# Apo_Board_2017_ATmega328SMD_PAM2401.net
KiCad netlist of a schematic drawn in EAGLE
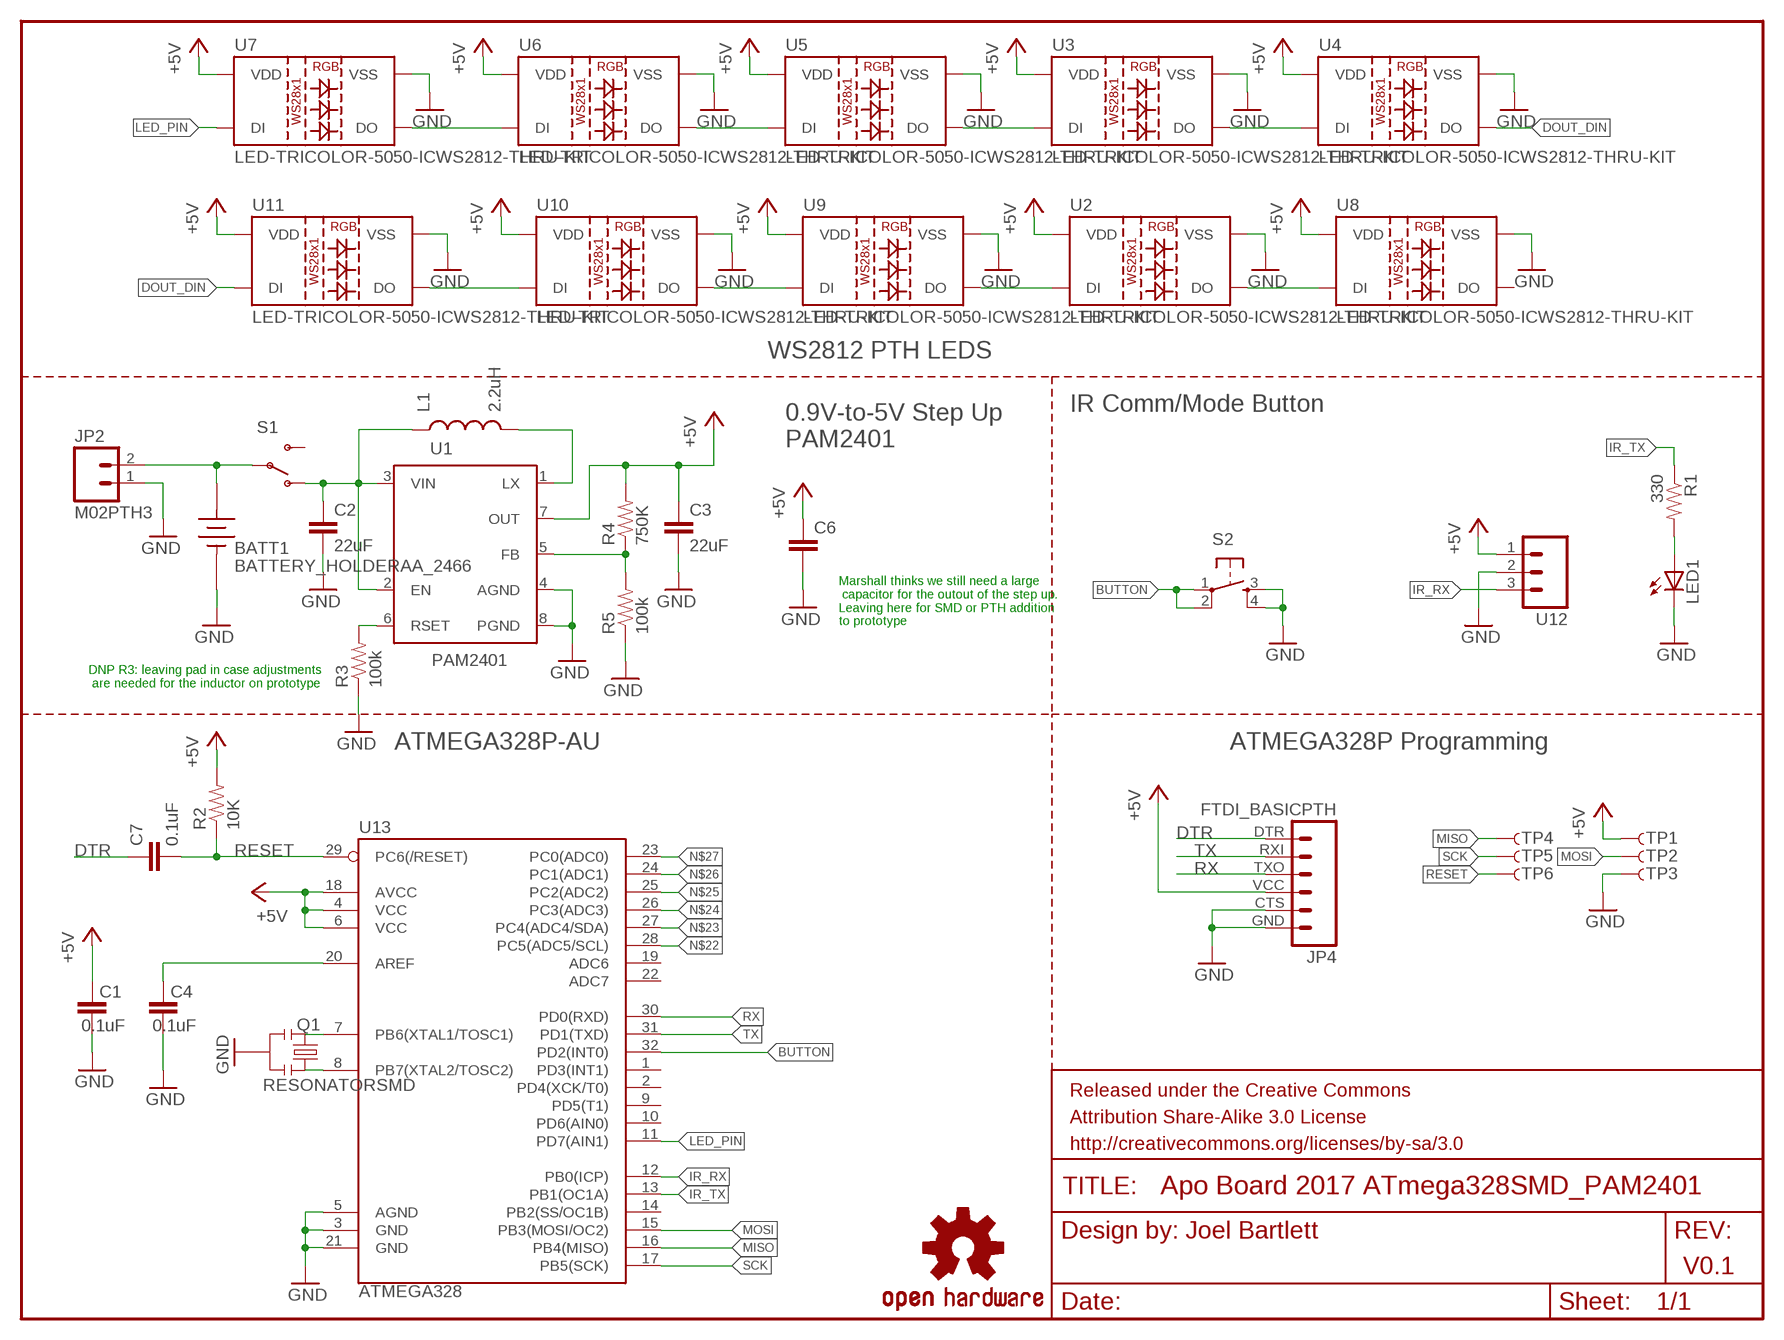
[diagram p0: schematic, sheet 1]

(export (version "E")
  (design (tool "Eeschema 10.0.6"))
  (components
    (comp (ref "BATT1")
      (value "BATTERY_HOLDERAA_2466")
      (footprint "eagle-import:BATT_HOLDER_AA_2466")
      (libsource (lib "eagle-import") (part "BATTERY_HOLDERAA_2466"))
    )
    (comp (ref "C1")
      (value "0.1uF")
      (footprint "eagle-import:0402-CAP")
      (libsource (lib "eagle-import") (part "CAP0402-CAP"))
    )
    (comp (ref "C2")
      (value "22uF")
      (footprint "eagle-import:0805")
      (libsource (lib "eagle-import") (part "22UF-6.3V-20%(0805)"))
    )
    (comp (ref "C3")
      (value "22uF")
      (footprint "eagle-import:0805")
      (libsource (lib "eagle-import") (part "22UF-6.3V-20%(0805)"))
    )
    (comp (ref "C4")
      (value "0.1uF")
      (footprint "eagle-import:0402-CAP")
      (libsource (lib "eagle-import") (part "CAP0402-CAP"))
    )
    (comp (ref "C6")
      (value "CAP1206")
      (footprint "eagle-import:1206")
      (libsource (lib "eagle-import") (part "SparkFun-Capacitors_CAP1206"))
    )
    (comp (ref "C7")
      (value "0.1uF")
      (footprint "eagle-import:0402-CAP")
      (libsource (lib "eagle-import") (part "CAP0402-CAP"))
    )
    (comp (ref "FRAME1")
      (value "FRAME-LETTER")
      (footprint "eagle-import:CREATIVE_COMMONS")
      (libsource (lib "eagle-import") (part "FRAME-LETTER"))
    )
    (comp (ref "JP2")
      (value "M02PTH3")
      (footprint "eagle-import:1X02_LONGPADS")
      (libsource (lib "eagle-import") (part "M02PTH3"))
    )
    (comp (ref "JP4")
      (value "FTDI_BASICPTH")
      (footprint "eagle-import:FTDI_BASIC")
      (libsource (lib "eagle-import") (part "FTDI_BASICPTH"))
    )
    (comp (ref "L1")
      (value "2.2uH")
      (footprint "eagle-import:CR54")
      (libsource (lib "eagle-import") (part "INDUCTORCR54"))
    )
    (comp (ref "LED1")
      (value "LED5MM-KIT")
      (footprint "eagle-import:LED5MM-KIT")
      (libsource (lib "eagle-import") (part "LED5MM-KIT"))
    )
    (comp (ref "LOGO1")
      (value "OSHW-LOGOS")
      (footprint "eagle-import:OSHW-LOGO-S")
      (libsource (lib "eagle-import") (part "OSHW-LOGOS"))
    )
    (comp (ref "Q1")
      (value "RESONATORSMD")
      (footprint "eagle-import:RESONATOR-SMD")
      (libsource (lib "eagle-import") (part "RESONATORSMD"))
    )
    (comp (ref "R1")
      (value "330")
      (footprint "eagle-import:AXIAL-0.3-KIT")
      (libsource (lib "eagle-import") (part "SparkFun-Resistors_RESISTORKIT"))
    )
    (comp (ref "R2")
      (value "10K")
      (footprint "eagle-import:0402-RES")
      (libsource (lib "eagle-import") (part "RESISTOR0402-RES"))
    )
    (comp (ref "R3")
      (value "100k")
      (footprint "eagle-import:0603-RES")
      (libsource (lib "eagle-import") (part "10K-1%RES-00824"))
    )
    (comp (ref "R4")
      (value "750K")
      (footprint "eagle-import:0603-RES")
      (libsource (lib "eagle-import") (part "10K-1%RES-00824"))
    )
    (comp (ref "R5")
      (value "100k")
      (footprint "eagle-import:0603-RES")
      (libsource (lib "eagle-import") (part "10K-1%RES-00824"))
    )
    (comp (ref "S1")
      (value "SWITCH-SPSTKIT")
      (footprint "eagle-import:SWITCH-SPDT_KIT")
      (libsource (lib "eagle-import") (part "SWITCH-SPSTKIT"))
    )
    (comp (ref "S2")
      (value "TAC_SWITCHPTH")
      (footprint "eagle-import:TACTILE-PTH")
      (libsource (lib "eagle-import") (part "TAC_SWITCHPTH"))
    )
    (comp (ref "TP1")
      (value "TP-3x5")
      (footprint "eagle-import:PAD.03X.05")
      (libsource (lib "eagle-import") (part "TEST-POINT3X5"))
    )
    (comp (ref "TP2")
      (value "TP-3x5")
      (footprint "eagle-import:PAD.03X.05")
      (libsource (lib "eagle-import") (part "TEST-POINT3X5"))
    )
    (comp (ref "TP3")
      (value "TP-3x5")
      (footprint "eagle-import:PAD.03X.05")
      (libsource (lib "eagle-import") (part "TEST-POINT3X5"))
    )
    (comp (ref "TP4")
      (value "TP-3x5")
      (footprint "eagle-import:PAD.03X.05")
      (libsource (lib "eagle-import") (part "TEST-POINT3X5"))
    )
    (comp (ref "TP5")
      (value "TP-3x5")
      (footprint "eagle-import:PAD.03X.05")
      (libsource (lib "eagle-import") (part "TEST-POINT3X5"))
    )
    (comp (ref "TP6")
      (value "TP-3x5")
      (footprint "eagle-import:PAD.03X.05")
      (libsource (lib "eagle-import") (part "TEST-POINT3X5"))
    )
    (comp (ref "U1")
      (value "PAM2401")
      (footprint "eagle-import:MSOP8")
      (libsource (lib "eagle-import") (part "PAM2401"))
    )
    (comp (ref "U2")
      (value "LED-TRICOLOR-5050-ICWS2812-THRU-KIT")
      (footprint "eagle-import:LED-RGB-THRU-KIT")
      (libsource (lib "eagle-import") (part "LED-TRICOLOR-5050-ICWS2812-THRU-KIT"))
    )
    (comp (ref "U3")
      (value "LED-TRICOLOR-5050-ICWS2812-THRU-KIT")
      (footprint "eagle-import:LED-RGB-THRU-KIT")
      (libsource (lib "eagle-import") (part "LED-TRICOLOR-5050-ICWS2812-THRU-KIT"))
    )
    (comp (ref "U4")
      (value "LED-TRICOLOR-5050-ICWS2812-THRU-KIT")
      (footprint "eagle-import:LED-RGB-THRU-KIT")
      (libsource (lib "eagle-import") (part "LED-TRICOLOR-5050-ICWS2812-THRU-KIT"))
    )
    (comp (ref "U5")
      (value "LED-TRICOLOR-5050-ICWS2812-THRU-KIT")
      (footprint "eagle-import:LED-RGB-THRU-KIT")
      (libsource (lib "eagle-import") (part "LED-TRICOLOR-5050-ICWS2812-THRU-KIT"))
    )
    (comp (ref "U6")
      (value "LED-TRICOLOR-5050-ICWS2812-THRU-KIT")
      (footprint "eagle-import:LED-RGB-THRU-KIT")
      (libsource (lib "eagle-import") (part "LED-TRICOLOR-5050-ICWS2812-THRU-KIT"))
    )
    (comp (ref "U7")
      (value "LED-TRICOLOR-5050-ICWS2812-THRU-KIT")
      (footprint "eagle-import:LED-RGB-THRU-KIT")
      (libsource (lib "eagle-import") (part "LED-TRICOLOR-5050-ICWS2812-THRU-KIT"))
    )
    (comp (ref "U8")
      (value "LED-TRICOLOR-5050-ICWS2812-THRU-KIT")
      (footprint "eagle-import:LED-RGB-THRU-KIT")
      (libsource (lib "eagle-import") (part "LED-TRICOLOR-5050-ICWS2812-THRU-KIT"))
    )
    (comp (ref "U9")
      (value "LED-TRICOLOR-5050-ICWS2812-THRU-KIT")
      (footprint "eagle-import:LED-RGB-THRU-KIT")
      (libsource (lib "eagle-import") (part "LED-TRICOLOR-5050-ICWS2812-THRU-KIT"))
    )
    (comp (ref "U10")
      (value "LED-TRICOLOR-5050-ICWS2812-THRU-KIT")
      (footprint "eagle-import:LED-RGB-THRU-KIT")
      (libsource (lib "eagle-import") (part "LED-TRICOLOR-5050-ICWS2812-THRU-KIT"))
    )
    (comp (ref "U11")
      (value "LED-TRICOLOR-5050-ICWS2812-THRU-KIT")
      (footprint "eagle-import:LED-RGB-THRU-KIT")
      (libsource (lib "eagle-import") (part "LED-TRICOLOR-5050-ICWS2812-THRU-KIT"))
    )
    (comp (ref "U12")
      (value "M03IR_RECEIVER")
      (footprint "eagle-import:1X03_IR_RECEIVER")
      (libsource (lib "eagle-import") (part "M03IR_RECEIVER"))
    )
    (comp (ref "U13")
      (value "ATMEGA328")
      (footprint "eagle-import:TQFP32-08")
      (libsource (lib "eagle-import") (part "ATMEGA168"))
    )
  )
  (nets
    (net (code "1") (name "+5V") (class "Default")
      (node (ref "C1") (pin "2") (pinfunction "2_2") (pintype "passive"))
      (node (ref "C3") (pin "1") (pinfunction "1_1") (pintype "passive"))
      (node (ref "C6") (pin "1") (pinfunction "1_1") (pintype "passive"))
      (node (ref "JP4") (pin "VCC") (pinfunction "4_VCC") (pintype "passive"))
      (node (ref "R2") (pin "2") (pinfunction "2_2") (pintype "passive"))
      (node (ref "R4") (pin "2") (pinfunction "2_2") (pintype "passive"))
      (node (ref "TP1") (pin "P$1") (pinfunction "1_P$1") (pintype "bidirectional"))
      (node (ref "U1") (pin "7") (pinfunction "OUT_7") (pintype "bidirectional"))
      (node (ref "U10") (pin "2") (pinfunction "VDD_2") (pintype "bidirectional"))
      (node (ref "U11") (pin "2") (pinfunction "VDD_2") (pintype "bidirectional"))
      (node (ref "U12") (pin "1") (pinfunction "1_1") (pintype "passive"))
      (node (ref "U13") (pin "18") (pinfunction "AVCC_18") (pintype "bidirectional"))
      (node (ref "U13") (pin "4") (pinfunction "VCC_4") (pintype "bidirectional"))
      (node (ref "U13") (pin "6") (pinfunction "VCC_6") (pintype "bidirectional"))
      (node (ref "U2") (pin "2") (pinfunction "VDD_2") (pintype "bidirectional"))
      (node (ref "U3") (pin "2") (pinfunction "VDD_2") (pintype "bidirectional"))
      (node (ref "U4") (pin "2") (pinfunction "VDD_2") (pintype "bidirectional"))
      (node (ref "U5") (pin "2") (pinfunction "VDD_2") (pintype "bidirectional"))
      (node (ref "U6") (pin "2") (pinfunction "VDD_2") (pintype "bidirectional"))
      (node (ref "U7") (pin "2") (pinfunction "VDD_2") (pintype "bidirectional"))
      (node (ref "U8") (pin "2") (pinfunction "VDD_2") (pintype "bidirectional"))
      (node (ref "U9") (pin "2") (pinfunction "VDD_2") (pintype "bidirectional"))
    )
    (net (code "2") (name "/DTR") (class "Default")
      (node (ref "C7") (pin "1") (pinfunction "1_1") (pintype "passive"))
      (node (ref "JP4") (pin "DTR") (pinfunction "1_DTR") (pintype "passive"))
    )
    (net (code "3") (name "BUTTON") (class "Default")
      (node (ref "S2") (pin "1") (pinfunction "1_1") (pintype "passive"))
      (node (ref "S2") (pin "2") (pinfunction "2_2") (pintype "passive"))
      (node (ref "U13") (pin "32") (pinfunction "PD2(INT0)_32") (pintype "bidirectional"))
    )
    (net (code "4") (name "DOUT_DIN") (class "Default")
      (node (ref "U11") (pin "1") (pinfunction "DI_1") (pintype "bidirectional"))
      (node (ref "U4") (pin "4") (pinfunction "DO_4") (pintype "bidirectional"))
    )
    (net (code "5") (name "GND") (class "Default")
      (node (ref "BATT1") (pin "N") (pinfunction "N_N") (pintype "bidirectional"))
      (node (ref "C1") (pin "1") (pinfunction "1_1") (pintype "passive"))
      (node (ref "C2") (pin "2") (pinfunction "2_2") (pintype "passive"))
      (node (ref "C3") (pin "2") (pinfunction "2_2") (pintype "passive"))
      (node (ref "C4") (pin "1") (pinfunction "1_1") (pintype "passive"))
      (node (ref "C6") (pin "2") (pinfunction "2_2") (pintype "passive"))
      (node (ref "JP2") (pin "1") (pinfunction "1_1") (pintype "passive"))
      (node (ref "JP4") (pin "CTS") (pinfunction "5_CTS") (pintype "passive"))
      (node (ref "JP4") (pin "GND") (pinfunction "6_GND") (pintype "passive"))
      (node (ref "LED1") (pin "K") (pinfunction "C_K") (pintype "passive"))
      (node (ref "Q1") (pin "2") (pinfunction "2_2") (pintype "passive"))
      (node (ref "R3") (pin "1") (pinfunction "1_1") (pintype "passive"))
      (node (ref "R5") (pin "1") (pinfunction "1_1") (pintype "passive"))
      (node (ref "S2") (pin "3") (pinfunction "3_3") (pintype "passive"))
      (node (ref "S2") (pin "4") (pinfunction "4_4") (pintype "passive"))
      (node (ref "TP3") (pin "P$1") (pinfunction "1_P$1") (pintype "bidirectional"))
      (node (ref "U1") (pin "4") (pinfunction "AGND_4") (pintype "bidirectional"))
      (node (ref "U1") (pin "8") (pinfunction "PGND_8") (pintype "bidirectional"))
      (node (ref "U10") (pin "3") (pinfunction "VSS_3") (pintype "bidirectional"))
      (node (ref "U11") (pin "3") (pinfunction "VSS_3") (pintype "bidirectional"))
      (node (ref "U12") (pin "2") (pinfunction "2_2") (pintype "passive"))
      (node (ref "U13") (pin "21") (pinfunction "GND_21") (pintype "bidirectional"))
      (node (ref "U13") (pin "3") (pinfunction "GND_3") (pintype "bidirectional"))
      (node (ref "U13") (pin "5") (pinfunction "AGND_5") (pintype "bidirectional"))
      (node (ref "U2") (pin "3") (pinfunction "VSS_3") (pintype "bidirectional"))
      (node (ref "U3") (pin "3") (pinfunction "VSS_3") (pintype "bidirectional"))
      (node (ref "U4") (pin "3") (pinfunction "VSS_3") (pintype "bidirectional"))
      (node (ref "U5") (pin "3") (pinfunction "VSS_3") (pintype "bidirectional"))
      (node (ref "U6") (pin "3") (pinfunction "VSS_3") (pintype "bidirectional"))
      (node (ref "U7") (pin "3") (pinfunction "VSS_3") (pintype "bidirectional"))
      (node (ref "U8") (pin "3") (pinfunction "VSS_3") (pintype "bidirectional"))
      (node (ref "U9") (pin "3") (pinfunction "VSS_3") (pintype "bidirectional"))
    )
    (net (code "6") (name "IR_RX") (class "Default")
      (node (ref "U12") (pin "3") (pinfunction "3_3") (pintype "passive"))
      (node (ref "U13") (pin "12") (pinfunction "PB0(ICP)_12") (pintype "bidirectional"))
    )
    (net (code "7") (name "IR_TX") (class "Default")
      (node (ref "R1") (pin "P$1") (pinfunction "1_P$1") (pintype "passive"))
      (node (ref "U13") (pin "13") (pinfunction "PB1(OC1A)_13") (pintype "bidirectional"))
    )
    (net (code "8") (name "LED_PIN") (class "Default")
      (node (ref "U13") (pin "11") (pinfunction "PD7(AIN1)_11") (pintype "bidirectional"))
      (node (ref "U7") (pin "1") (pinfunction "DI_1") (pintype "bidirectional"))
    )
    (net (code "9") (name "MISO") (class "Default")
      (node (ref "TP4") (pin "P$1") (pinfunction "1_P$1") (pintype "bidirectional"))
      (node (ref "U13") (pin "16") (pinfunction "PB4(MISO)_16") (pintype "bidirectional"))
    )
    (net (code "10") (name "MOSI") (class "Default")
      (node (ref "TP2") (pin "P$1") (pinfunction "1_P$1") (pintype "bidirectional"))
      (node (ref "U13") (pin "15") (pinfunction "PB3(MOSI/OC2)_15") (pintype "bidirectional"))
    )
    (net (code "11") (name "N$22") (class "Default")
      (node (ref "U13") (pin "28") (pinfunction "PC5(ADC5/SCL)_28") (pintype "bidirectional"))
    )
    (net (code "12") (name "N$23") (class "Default")
      (node (ref "U13") (pin "27") (pinfunction "PC4(ADC4/SDA)_27") (pintype "bidirectional"))
    )
    (net (code "13") (name "N$24") (class "Default")
      (node (ref "U13") (pin "26") (pinfunction "PC3(ADC3)_26") (pintype "bidirectional"))
    )
    (net (code "14") (name "N$25") (class "Default")
      (node (ref "U13") (pin "25") (pinfunction "PC2(ADC2)_25") (pintype "bidirectional"))
    )
    (net (code "15") (name "N$26") (class "Default")
      (node (ref "U13") (pin "24") (pinfunction "PC1(ADC1)_24") (pintype "bidirectional"))
    )
    (net (code "16") (name "N$27") (class "Default")
      (node (ref "U13") (pin "23") (pinfunction "PC0(ADC0)_23") (pintype "bidirectional"))
    )
    (net (code "17") (name "Net-(L1-1)") (class "Default")
      (node (ref "C2") (pin "1") (pinfunction "1_1") (pintype "passive"))
      (node (ref "L1") (pin "P$1") (pinfunction "1_P$1") (pintype "passive"))
      (node (ref "S1") (pin "1") (pinfunction "O_1") (pintype "passive"))
      (node (ref "U1") (pin "2") (pinfunction "EN_2") (pintype "bidirectional"))
      (node (ref "U1") (pin "3") (pinfunction "VIN_3") (pintype "bidirectional"))
    )
    (net (code "18") (name "Net-(L1-2)") (class "Default")
      (node (ref "L1") (pin "P$2") (pinfunction "2_P$2") (pintype "passive"))
      (node (ref "U1") (pin "1") (pinfunction "LX_1") (pintype "bidirectional"))
    )
    (net (code "19") (name "Net-(R1-2)") (class "Default")
      (node (ref "LED1") (pin "A") (pinfunction "A_A") (pintype "passive"))
      (node (ref "R1") (pin "P$2") (pinfunction "2_P$2") (pintype "passive"))
    )
    (net (code "20") (name "Net-(S1-P)") (class "Default")
      (node (ref "BATT1") (pin "P") (pinfunction "P_P") (pintype "bidirectional"))
      (node (ref "JP2") (pin "2") (pinfunction "2_2") (pintype "passive"))
      (node (ref "S1") (pin "2") (pinfunction "P_2") (pintype "passive"))
    )
    (net (code "21") (name "Net-(U1-FB)") (class "Default")
      (node (ref "R4") (pin "1") (pinfunction "1_1") (pintype "passive"))
      (node (ref "R5") (pin "2") (pinfunction "2_2") (pintype "passive"))
      (node (ref "U1") (pin "5") (pinfunction "FB_5") (pintype "bidirectional"))
    )
    (net (code "22") (name "Net-(U1-RSET)") (class "Default")
      (node (ref "R3") (pin "2") (pinfunction "2_2") (pintype "passive"))
      (node (ref "U1") (pin "6") (pinfunction "RSET_6") (pintype "bidirectional"))
    )
    (net (code "23") (name "Net-(U2-DI)") (class "Default")
      (node (ref "U2") (pin "1") (pinfunction "DI_1") (pintype "bidirectional"))
      (node (ref "U9") (pin "4") (pinfunction "DO_4") (pintype "bidirectional"))
    )
    (net (code "24") (name "Net-(U2-DO)") (class "Default")
      (node (ref "U2") (pin "4") (pinfunction "DO_4") (pintype "bidirectional"))
      (node (ref "U8") (pin "1") (pinfunction "DI_1") (pintype "bidirectional"))
    )
    (net (code "25") (name "Net-(U3-DI)") (class "Default")
      (node (ref "U3") (pin "1") (pinfunction "DI_1") (pintype "bidirectional"))
      (node (ref "U5") (pin "4") (pinfunction "DO_4") (pintype "bidirectional"))
    )
    (net (code "26") (name "Net-(U3-DO)") (class "Default")
      (node (ref "U3") (pin "4") (pinfunction "DO_4") (pintype "bidirectional"))
      (node (ref "U4") (pin "1") (pinfunction "DI_1") (pintype "bidirectional"))
    )
    (net (code "27") (name "Net-(U5-DI)") (class "Default")
      (node (ref "U5") (pin "1") (pinfunction "DI_1") (pintype "bidirectional"))
      (node (ref "U6") (pin "4") (pinfunction "DO_4") (pintype "bidirectional"))
    )
    (net (code "28") (name "Net-(U6-DI)") (class "Default")
      (node (ref "U6") (pin "1") (pinfunction "DI_1") (pintype "bidirectional"))
      (node (ref "U7") (pin "4") (pinfunction "DO_4") (pintype "bidirectional"))
    )
    (net (code "29") (name "Net-(U10-DI)") (class "Default")
      (node (ref "U10") (pin "1") (pinfunction "DI_1") (pintype "bidirectional"))
      (node (ref "U11") (pin "4") (pinfunction "DO_4") (pintype "bidirectional"))
    )
    (net (code "30") (name "Net-(U10-DO)") (class "Default")
      (node (ref "U10") (pin "4") (pinfunction "DO_4") (pintype "bidirectional"))
      (node (ref "U9") (pin "1") (pinfunction "DI_1") (pintype "bidirectional"))
    )
    (net (code "31") (name "Net-(U13-AREF)") (class "Default")
      (node (ref "C4") (pin "2") (pinfunction "2_2") (pintype "passive"))
      (node (ref "U13") (pin "20") (pinfunction "AREF_20") (pintype "bidirectional"))
    )
    (net (code "32") (name "Net-(U13-PB6(XTAL1{slash}TOSC1))") (class "Default")
      (node (ref "Q1") (pin "3") (pinfunction "3_3") (pintype "passive"))
      (node (ref "U13") (pin "7") (pinfunction "PB6(XTAL1/TOSC1)_7") (pintype "bidirectional"))
    )
    (net (code "33") (name "Net-(U13-PB7(XTAL2{slash}TOSC2))") (class "Default")
      (node (ref "Q1") (pin "1") (pinfunction "1_1") (pintype "passive"))
      (node (ref "U13") (pin "8") (pinfunction "PB7(XTAL2/TOSC2)_8") (pintype "bidirectional"))
    )
    (net (code "34") (name "RESET") (class "Default")
      (node (ref "C7") (pin "2") (pinfunction "2_2") (pintype "passive"))
      (node (ref "R2") (pin "1") (pinfunction "1_1") (pintype "passive"))
      (node (ref "TP6") (pin "P$1") (pinfunction "1_P$1") (pintype "bidirectional"))
      (node (ref "U13") (pin "29") (pinfunction "PC6(/RESET)_29") (pintype "bidirectional"))
    )
    (net (code "35") (name "RX") (class "Default")
      (node (ref "JP4") (pin "TXO") (pinfunction "3_TXO") (pintype "passive"))
      (node (ref "U13") (pin "30") (pinfunction "PD0(RXD)_30") (pintype "bidirectional"))
    )
    (net (code "36") (name "SCK") (class "Default")
      (node (ref "TP5") (pin "P$1") (pinfunction "1_P$1") (pintype "bidirectional"))
      (node (ref "U13") (pin "17") (pinfunction "PB5(SCK)_17") (pintype "bidirectional"))
    )
    (net (code "37") (name "TX") (class "Default")
      (node (ref "JP4") (pin "RXI") (pinfunction "2_RXI") (pintype "passive"))
      (node (ref "U13") (pin "31") (pinfunction "PD1(TXD)_31") (pintype "bidirectional"))
    )
    (net (code "38") (name "unconnected-(S1-S-Pad3)") (class "Default")
      (node (ref "S1") (pin "3") (pinfunction "S_3") (pintype "passive"))
    )
    (net (code "39") (name "unconnected-(U8-DO-Pad4)") (class "Default")
      (node (ref "U8") (pin "4") (pinfunction "DO_4") (pintype "bidirectional"))
    )
    (net (code "40") (name "unconnected-(U13-ADC6-Pad19)") (class "Default")
      (node (ref "U13") (pin "19") (pinfunction "ADC6_19") (pintype "bidirectional"))
    )
    (net (code "41") (name "unconnected-(U13-ADC7-Pad22)") (class "Default")
      (node (ref "U13") (pin "22") (pinfunction "ADC7_22") (pintype "bidirectional"))
    )
    (net (code "42") (name "unconnected-(U13-PB2(SS{slash}OC1B)-Pad14)") (class "Default")
      (node (ref "U13") (pin "14") (pinfunction "PB2(SS/OC1B)_14") (pintype "bidirectional"))
    )
    (net (code "43") (name "unconnected-(U13-PD3(INT1)-Pad1)") (class "Default")
      (node (ref "U13") (pin "1") (pinfunction "PD3(INT1)_1") (pintype "bidirectional"))
    )
    (net (code "44") (name "unconnected-(U13-PD4(XCK{slash}T0)-Pad2)") (class "Default")
      (node (ref "U13") (pin "2") (pinfunction "PD4(XCK/T0)_2") (pintype "bidirectional"))
    )
    (net (code "45") (name "unconnected-(U13-PD5(T1)-Pad9)") (class "Default")
      (node (ref "U13") (pin "9") (pinfunction "PD5(T1)_9") (pintype "bidirectional"))
    )
    (net (code "46") (name "unconnected-(U13-PD6(AIN0)-Pad10)") (class "Default")
      (node (ref "U13") (pin "10") (pinfunction "PD6(AIN0)_10") (pintype "bidirectional"))
    )
  )
)
